# vram_old.net
KiCad netlist of a schematic drawn in Altium Designer
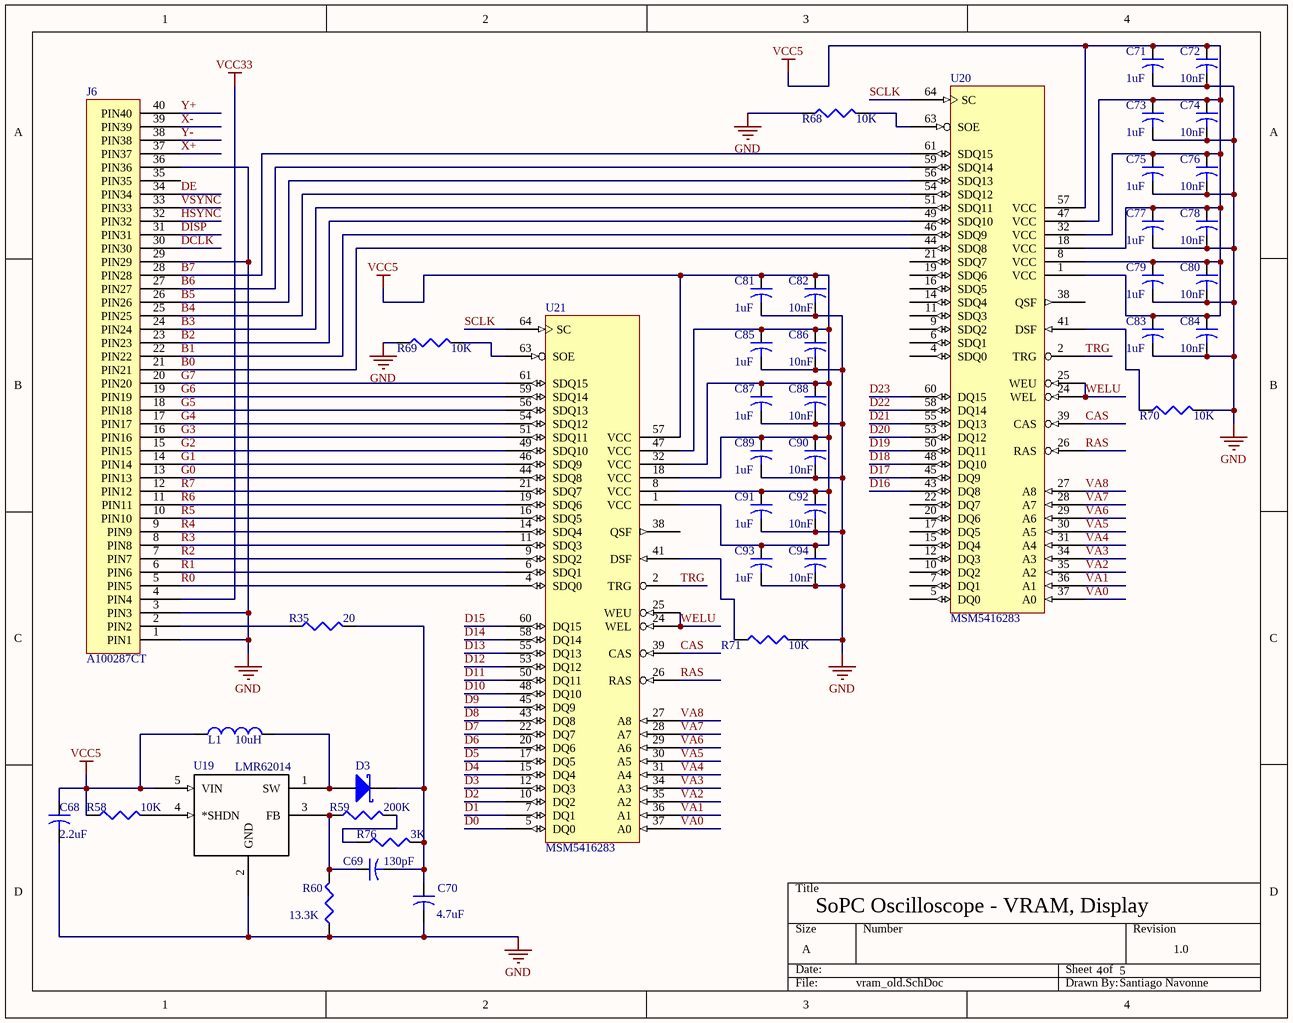
[diagram p0: vram_old.SchDoc]

(export (version "E")
  (design (tool "Eeschema 10.0.6"))
  (components
    (comp (ref "C68")
      (value "2.2uF")
      (footprint "CAPC1608L")
      (description "Capacitor")
      (fields (field (name "Comment") "Cap2") (field (name "PUBLISHER") "Altium Limited"))
      (libsource (lib "Miscellaneous Devices") (part "Cap2"))
    )
    (comp (ref "C69")
      (value "130pF")
      (footprint "CAPC2012N")
      (description "Capacitor")
      (fields (field (name "Comment") "Cap2") (field (name "PUBLISHER") "Altium Limited"))
      (libsource (lib "Miscellaneous Devices") (part "Cap2"))
    )
    (comp (ref "C70")
      (value "4.7uF")
      (footprint "CAPC1608L")
      (description "Capacitor")
      (fields (field (name "Comment") "Cap2") (field (name "PUBLISHER") "Altium Limited"))
      (libsource (lib "Miscellaneous Devices") (part "Cap2"))
    )
    (comp (ref "C71")
      (value "1uF")
      (footprint "CAPC1608L")
      (description "Capacitor")
      (fields (field (name "Comment") "Cap2") (field (name "PUBLISHER") "Altium Limited"))
      (libsource (lib "Miscellaneous Devices") (part "Cap2"))
    )
    (comp (ref "C72")
      (value "10nF")
      (footprint "CAPC1608L")
      (description "Capacitor")
      (fields (field (name "Comment") "Cap2") (field (name "PUBLISHER") "Altium Limited"))
      (libsource (lib "Miscellaneous Devices") (part "Cap2"))
    )
    (comp (ref "C73")
      (value "1uF")
      (footprint "CAPC1608L")
      (description "Capacitor")
      (fields (field (name "Comment") "Cap2") (field (name "PUBLISHER") "Altium Limited"))
      (libsource (lib "Miscellaneous Devices") (part "Cap2"))
    )
    (comp (ref "C74")
      (value "10nF")
      (footprint "CAPC1608L")
      (description "Capacitor")
      (fields (field (name "Comment") "Cap2") (field (name "PUBLISHER") "Altium Limited"))
      (libsource (lib "Miscellaneous Devices") (part "Cap2"))
    )
    (comp (ref "C75")
      (value "1uF")
      (footprint "CAPC1608L")
      (description "Capacitor")
      (fields (field (name "Comment") "Cap2") (field (name "PUBLISHER") "Altium Limited"))
      (libsource (lib "Miscellaneous Devices") (part "Cap2"))
    )
    (comp (ref "C76")
      (value "10nF")
      (footprint "CAPC1608L")
      (description "Capacitor")
      (fields (field (name "Comment") "Cap2") (field (name "PUBLISHER") "Altium Limited"))
      (libsource (lib "Miscellaneous Devices") (part "Cap2"))
    )
    (comp (ref "C77")
      (value "1uF")
      (footprint "CAPC1608L")
      (description "Capacitor")
      (fields (field (name "Comment") "Cap2") (field (name "PUBLISHER") "Altium Limited"))
      (libsource (lib "Miscellaneous Devices") (part "Cap2"))
    )
    (comp (ref "C78")
      (value "10nF")
      (footprint "CAPC1608L")
      (description "Capacitor")
      (fields (field (name "Comment") "Cap2") (field (name "PUBLISHER") "Altium Limited"))
      (libsource (lib "Miscellaneous Devices") (part "Cap2"))
    )
    (comp (ref "C79")
      (value "1uF")
      (footprint "CAPC1608L")
      (description "Capacitor")
      (fields (field (name "Comment") "Cap2") (field (name "PUBLISHER") "Altium Limited"))
      (libsource (lib "Miscellaneous Devices") (part "Cap2"))
    )
    (comp (ref "C80")
      (value "10nF")
      (footprint "CAPC1608L")
      (description "Capacitor")
      (fields (field (name "Comment") "Cap2") (field (name "PUBLISHER") "Altium Limited"))
      (libsource (lib "Miscellaneous Devices") (part "Cap2"))
    )
    (comp (ref "C81")
      (value "1uF")
      (footprint "CAPC1608L")
      (description "Capacitor")
      (fields (field (name "Comment") "Cap2") (field (name "PUBLISHER") "Altium Limited"))
      (libsource (lib "Miscellaneous Devices") (part "Cap2"))
    )
    (comp (ref "C82")
      (value "10nF")
      (footprint "CAPC1608L")
      (description "Capacitor")
      (fields (field (name "Comment") "Cap2") (field (name "PUBLISHER") "Altium Limited"))
      (libsource (lib "Miscellaneous Devices") (part "Cap2"))
    )
    (comp (ref "C83")
      (value "1uF")
      (footprint "CAPC1608L")
      (description "Capacitor")
      (fields (field (name "Comment") "Cap2") (field (name "PUBLISHER") "Altium Limited"))
      (libsource (lib "Miscellaneous Devices") (part "Cap2"))
    )
    (comp (ref "C84")
      (value "10nF")
      (footprint "CAPC1608L")
      (description "Capacitor")
      (fields (field (name "Comment") "Cap2") (field (name "PUBLISHER") "Altium Limited"))
      (libsource (lib "Miscellaneous Devices") (part "Cap2"))
    )
    (comp (ref "C85")
      (value "1uF")
      (footprint "CAPC1608L")
      (description "Capacitor")
      (fields (field (name "Comment") "Cap2") (field (name "PUBLISHER") "Altium Limited"))
      (libsource (lib "Miscellaneous Devices") (part "Cap2"))
    )
    (comp (ref "C86")
      (value "10nF")
      (footprint "CAPC1608L")
      (description "Capacitor")
      (fields (field (name "Comment") "Cap2") (field (name "PUBLISHER") "Altium Limited"))
      (libsource (lib "Miscellaneous Devices") (part "Cap2"))
    )
    (comp (ref "C87")
      (value "1uF")
      (footprint "CAPC1608L")
      (description "Capacitor")
      (fields (field (name "Comment") "Cap2") (field (name "PUBLISHER") "Altium Limited"))
      (libsource (lib "Miscellaneous Devices") (part "Cap2"))
    )
    (comp (ref "C88")
      (value "10nF")
      (footprint "CAPC1608L")
      (description "Capacitor")
      (fields (field (name "Comment") "Cap2") (field (name "PUBLISHER") "Altium Limited"))
      (libsource (lib "Miscellaneous Devices") (part "Cap2"))
    )
    (comp (ref "C89")
      (value "1uF")
      (footprint "CAPC1608L")
      (description "Capacitor")
      (fields (field (name "Comment") "Cap2") (field (name "PUBLISHER") "Altium Limited"))
      (libsource (lib "Miscellaneous Devices") (part "Cap2"))
    )
    (comp (ref "C90")
      (value "10nF")
      (footprint "CAPC1608L")
      (description "Capacitor")
      (fields (field (name "Comment") "Cap2") (field (name "PUBLISHER") "Altium Limited"))
      (libsource (lib "Miscellaneous Devices") (part "Cap2"))
    )
    (comp (ref "C91")
      (value "1uF")
      (footprint "CAPC1608L")
      (description "Capacitor")
      (fields (field (name "Comment") "Cap2") (field (name "PUBLISHER") "Altium Limited"))
      (libsource (lib "Miscellaneous Devices") (part "Cap2"))
    )
    (comp (ref "C92")
      (value "10nF")
      (footprint "CAPC1608L")
      (description "Capacitor")
      (fields (field (name "Comment") "Cap2") (field (name "PUBLISHER") "Altium Limited"))
      (libsource (lib "Miscellaneous Devices") (part "Cap2"))
    )
    (comp (ref "C93")
      (value "1uF")
      (footprint "CAPC1608L")
      (description "Capacitor")
      (fields (field (name "Comment") "Cap2") (field (name "PUBLISHER") "Altium Limited"))
      (libsource (lib "Miscellaneous Devices") (part "Cap2"))
    )
    (comp (ref "C94")
      (value "10nF")
      (footprint "CAPC1608L")
      (description "Capacitor")
      (fields (field (name "Comment") "Cap2") (field (name "PUBLISHER") "Altium Limited"))
      (libsource (lib "Miscellaneous Devices") (part "Cap2"))
    )
    (comp (ref "D3")
      (value "D Schottky")
      (footprint "PowerDI123")
      (description "Schottky Diode")
      (fields (field (name "PUBLISHER") "Altium Limited"))
      (libsource (lib "Miscellaneous Devices") (part "D Schottky"))
    )
    (comp (ref "J6")
      (value "A100287CT")
      (footprint "FPC40")
      (libsource (lib "ee52_tago_sch") (part "A100287CT"))
    )
    (comp (ref "L1")
      (value "10uH")
      (footprint "lsdr0703")
      (description "Inductor")
      (fields (field (name "PUBLISHER") "Altium Limited"))
      (libsource (lib "Miscellaneous Devices") (part "Inductor"))
    )
    (comp (ref "R35")
      (value "20")
      (footprint "RESC1608N")
      (description "Resistor")
      (fields (field (name "Comment") "Res3") (field (name "PUBLISHER") "Altium Limited"))
      (libsource (lib "Miscellaneous Devices") (part "Res3"))
    )
    (comp (ref "R58")
      (value "10K")
      (footprint "RESC1608N")
      (description "Resistor")
      (fields (field (name "Comment") "Res3") (field (name "PUBLISHER") "Altium Limited"))
      (libsource (lib "Miscellaneous Devices") (part "Res3"))
    )
    (comp (ref "R59")
      (value "200K")
      (footprint "RESC1608N")
      (description "Resistor")
      (fields (field (name "Comment") "Res3") (field (name "PUBLISHER") "Altium Limited"))
      (libsource (lib "Miscellaneous Devices") (part "Res3"))
    )
    (comp (ref "R60")
      (value "13.3K")
      (footprint "RESC1608N")
      (description "Resistor")
      (fields (field (name "Comment") "Res3") (field (name "PUBLISHER") "Altium Limited"))
      (libsource (lib "Miscellaneous Devices") (part "Res3"))
    )
    (comp (ref "R68")
      (value "10K")
      (footprint "RESC1608N")
      (description "Resistor")
      (fields (field (name "Comment") "Res3") (field (name "PUBLISHER") "Altium Limited"))
      (libsource (lib "Miscellaneous Devices") (part "Res3"))
    )
    (comp (ref "R69")
      (value "10K")
      (footprint "RESC1608N")
      (description "Resistor")
      (fields (field (name "Comment") "Res3") (field (name "PUBLISHER") "Altium Limited"))
      (libsource (lib "Miscellaneous Devices") (part "Res3"))
    )
    (comp (ref "R70")
      (value "10K")
      (footprint "RESC1608N")
      (description "Resistor")
      (fields (field (name "Comment") "Res3") (field (name "PUBLISHER") "Altium Limited"))
      (libsource (lib "Miscellaneous Devices") (part "Res3"))
    )
    (comp (ref "R71")
      (value "10K")
      (footprint "RESC1608N")
      (description "Resistor")
      (fields (field (name "Comment") "Res3") (field (name "PUBLISHER") "Altium Limited"))
      (libsource (lib "Miscellaneous Devices") (part "Res3"))
    )
    (comp (ref "R76")
      (value "3K")
      (footprint "RESC1608N")
      (description "Resistor")
      (fields (field (name "Comment") "Res3") (field (name "PUBLISHER") "Altium Limited"))
      (libsource (lib "Miscellaneous Devices") (part "Res3"))
    )
    (comp (ref "U19")
      (value "LMR62014")
      (footprint "MF05A")
      (description "Imported")
      (fields
        (field (name "MANUFACTURER") "Texas Instruments")
        (field (name "MANUFACTURER_PART_NUMBER") "lmr62014_dbv_5")
      )
      (libsource (lib "2014-02-09_14-03-09") (part "LMR62014_DBV_5"))
    )
    (comp (ref "U20")
      (value "MSM5416283")
      (footprint "SSOP64")
      (description "262,144-Word x 16-Bit Multiport DRAM")
      (libsource (lib "eecs5x") (part "MSM5416283"))
    )
    (comp (ref "U21")
      (value "MSM5416283")
      (footprint "SSOP64")
      (description "262,144-Word x 16-Bit Multiport DRAM")
      (libsource (lib "eecs5x") (part "MSM5416283"))
    )
  )
  (nets
    (net (code "1") (name "/B0") (class "Default")
      (node (ref "J6") (pin "21") (pinfunction "PIN21_21") (pintype "passive"))
      (node (ref "U20") (pin "44") (pinfunction "SDQ8_44") (pintype "bidirectional"))
    )
    (net (code "2") (name "/B1") (class "Default")
      (node (ref "J6") (pin "22") (pinfunction "PIN22_22") (pintype "passive"))
      (node (ref "U20") (pin "46") (pinfunction "SDQ9_46") (pintype "bidirectional"))
    )
    (net (code "3") (name "/B2") (class "Default")
      (node (ref "J6") (pin "23") (pinfunction "PIN23_23") (pintype "passive"))
      (node (ref "U20") (pin "49") (pinfunction "SDQ10_49") (pintype "bidirectional"))
    )
    (net (code "4") (name "/B3") (class "Default")
      (node (ref "J6") (pin "24") (pinfunction "PIN24_24") (pintype "passive"))
      (node (ref "U20") (pin "51") (pinfunction "SDQ11_51") (pintype "bidirectional"))
    )
    (net (code "5") (name "/B4") (class "Default")
      (node (ref "J6") (pin "25") (pinfunction "PIN25_25") (pintype "passive"))
      (node (ref "U20") (pin "54") (pinfunction "SDQ12_54") (pintype "bidirectional"))
    )
    (net (code "6") (name "/B5") (class "Default")
      (node (ref "J6") (pin "26") (pinfunction "PIN26_26") (pintype "passive"))
      (node (ref "U20") (pin "56") (pinfunction "SDQ13_56") (pintype "bidirectional"))
    )
    (net (code "7") (name "/B6") (class "Default")
      (node (ref "J6") (pin "27") (pinfunction "PIN27_27") (pintype "passive"))
      (node (ref "U20") (pin "59") (pinfunction "SDQ14_59") (pintype "bidirectional"))
    )
    (net (code "8") (name "/B7") (class "Default")
      (node (ref "J6") (pin "28") (pinfunction "PIN28_28") (pintype "passive"))
      (node (ref "U20") (pin "61") (pinfunction "SDQ15_61") (pintype "bidirectional"))
    )
    (net (code "9") (name "/CAS") (class "Default")
      (node (ref "U20") (pin "39") (pinfunction "CAS_39") (pintype "input"))
      (node (ref "U21") (pin "39") (pinfunction "CAS_39") (pintype "input"))
    )
    (net (code "10") (name "/D0") (class "Default")
      (node (ref "U21") (pin "5") (pinfunction "DQ0_5") (pintype "bidirectional"))
    )
    (net (code "11") (name "/D1") (class "Default")
      (node (ref "U21") (pin "7") (pinfunction "DQ1_7") (pintype "bidirectional"))
    )
    (net (code "12") (name "/D2") (class "Default")
      (node (ref "U21") (pin "10") (pinfunction "DQ2_10") (pintype "bidirectional"))
    )
    (net (code "13") (name "/D3") (class "Default")
      (node (ref "U21") (pin "12") (pinfunction "DQ3_12") (pintype "bidirectional"))
    )
    (net (code "14") (name "/D4") (class "Default")
      (node (ref "U21") (pin "15") (pinfunction "DQ4_15") (pintype "bidirectional"))
    )
    (net (code "15") (name "/D5") (class "Default")
      (node (ref "U21") (pin "17") (pinfunction "DQ5_17") (pintype "bidirectional"))
    )
    (net (code "16") (name "/D6") (class "Default")
      (node (ref "U21") (pin "20") (pinfunction "DQ6_20") (pintype "bidirectional"))
    )
    (net (code "17") (name "/D7") (class "Default")
      (node (ref "U21") (pin "22") (pinfunction "DQ7_22") (pintype "bidirectional"))
    )
    (net (code "18") (name "/D8") (class "Default")
      (node (ref "U21") (pin "43") (pinfunction "DQ8_43") (pintype "bidirectional"))
    )
    (net (code "19") (name "/D9") (class "Default")
      (node (ref "U21") (pin "45") (pinfunction "DQ9_45") (pintype "bidirectional"))
    )
    (net (code "20") (name "/D10") (class "Default")
      (node (ref "U21") (pin "48") (pinfunction "DQ10_48") (pintype "bidirectional"))
    )
    (net (code "21") (name "/D11") (class "Default")
      (node (ref "U21") (pin "50") (pinfunction "DQ11_50") (pintype "bidirectional"))
    )
    (net (code "22") (name "/D12") (class "Default")
      (node (ref "U21") (pin "53") (pinfunction "DQ12_53") (pintype "bidirectional"))
    )
    (net (code "23") (name "/D13") (class "Default")
      (node (ref "U21") (pin "55") (pinfunction "DQ13_55") (pintype "bidirectional"))
    )
    (net (code "24") (name "/D14") (class "Default")
      (node (ref "U21") (pin "58") (pinfunction "DQ14_58") (pintype "bidirectional"))
    )
    (net (code "25") (name "/D15") (class "Default")
      (node (ref "U21") (pin "60") (pinfunction "DQ15_60") (pintype "bidirectional"))
    )
    (net (code "26") (name "/D16") (class "Default")
      (node (ref "U20") (pin "43") (pinfunction "DQ8_43") (pintype "bidirectional"))
    )
    (net (code "27") (name "/D17") (class "Default")
      (node (ref "U20") (pin "45") (pinfunction "DQ9_45") (pintype "bidirectional"))
    )
    (net (code "28") (name "/D18") (class "Default")
      (node (ref "U20") (pin "48") (pinfunction "DQ10_48") (pintype "bidirectional"))
    )
    (net (code "29") (name "/D19") (class "Default")
      (node (ref "U20") (pin "50") (pinfunction "DQ11_50") (pintype "bidirectional"))
    )
    (net (code "30") (name "/D20") (class "Default")
      (node (ref "U20") (pin "53") (pinfunction "DQ12_53") (pintype "bidirectional"))
    )
    (net (code "31") (name "/D21") (class "Default")
      (node (ref "U20") (pin "55") (pinfunction "DQ13_55") (pintype "bidirectional"))
    )
    (net (code "32") (name "/D22") (class "Default")
      (node (ref "U20") (pin "58") (pinfunction "DQ14_58") (pintype "bidirectional"))
    )
    (net (code "33") (name "/D23") (class "Default")
      (node (ref "U20") (pin "60") (pinfunction "DQ15_60") (pintype "bidirectional"))
    )
    (net (code "34") (name "/DCLK") (class "Default")
      (node (ref "J6") (pin "30") (pinfunction "PIN30_30") (pintype "passive"))
    )
    (net (code "35") (name "/DE") (class "Default")
      (node (ref "J6") (pin "34") (pinfunction "PIN34_34") (pintype "passive"))
    )
    (net (code "36") (name "/DISP") (class "Default")
      (node (ref "J6") (pin "31") (pinfunction "PIN31_31") (pintype "passive"))
    )
    (net (code "37") (name "/G0") (class "Default")
      (node (ref "J6") (pin "13") (pinfunction "PIN13_13") (pintype "passive"))
      (node (ref "U21") (pin "44") (pinfunction "SDQ8_44") (pintype "bidirectional"))
    )
    (net (code "38") (name "/G1") (class "Default")
      (node (ref "J6") (pin "14") (pinfunction "PIN14_14") (pintype "passive"))
      (node (ref "U21") (pin "46") (pinfunction "SDQ9_46") (pintype "bidirectional"))
    )
    (net (code "39") (name "/G2") (class "Default")
      (node (ref "J6") (pin "15") (pinfunction "PIN15_15") (pintype "passive"))
      (node (ref "U21") (pin "49") (pinfunction "SDQ10_49") (pintype "bidirectional"))
    )
    (net (code "40") (name "/G3") (class "Default")
      (node (ref "J6") (pin "16") (pinfunction "PIN16_16") (pintype "passive"))
      (node (ref "U21") (pin "51") (pinfunction "SDQ11_51") (pintype "bidirectional"))
    )
    (net (code "41") (name "/G4") (class "Default")
      (node (ref "J6") (pin "17") (pinfunction "PIN17_17") (pintype "passive"))
      (node (ref "U21") (pin "54") (pinfunction "SDQ12_54") (pintype "bidirectional"))
    )
    (net (code "42") (name "/G5") (class "Default")
      (node (ref "J6") (pin "18") (pinfunction "PIN18_18") (pintype "passive"))
      (node (ref "U21") (pin "56") (pinfunction "SDQ13_56") (pintype "bidirectional"))
    )
    (net (code "43") (name "/G6") (class "Default")
      (node (ref "J6") (pin "19") (pinfunction "PIN19_19") (pintype "passive"))
      (node (ref "U21") (pin "59") (pinfunction "SDQ14_59") (pintype "bidirectional"))
    )
    (net (code "44") (name "/G7") (class "Default")
      (node (ref "J6") (pin "20") (pinfunction "PIN20_20") (pintype "passive"))
      (node (ref "U21") (pin "61") (pinfunction "SDQ15_61") (pintype "bidirectional"))
    )
    (net (code "45") (name "/HSYNC") (class "Default")
      (node (ref "J6") (pin "32") (pinfunction "PIN32_32") (pintype "passive"))
    )
    (net (code "46") (name "/R0") (class "Default")
      (node (ref "J6") (pin "5") (pinfunction "PIN5_5") (pintype "passive"))
      (node (ref "U21") (pin "4") (pinfunction "SDQ0_4") (pintype "bidirectional"))
    )
    (net (code "47") (name "/R1") (class "Default")
      (node (ref "J6") (pin "6") (pinfunction "PIN6_6") (pintype "passive"))
      (node (ref "U21") (pin "6") (pinfunction "SDQ1_6") (pintype "bidirectional"))
    )
    (net (code "48") (name "/R2") (class "Default")
      (node (ref "J6") (pin "7") (pinfunction "PIN7_7") (pintype "passive"))
      (node (ref "U21") (pin "9") (pinfunction "SDQ2_9") (pintype "bidirectional"))
    )
    (net (code "49") (name "/R3") (class "Default")
      (node (ref "J6") (pin "8") (pinfunction "PIN8_8") (pintype "passive"))
      (node (ref "U21") (pin "11") (pinfunction "SDQ3_11") (pintype "bidirectional"))
    )
    (net (code "50") (name "/R4") (class "Default")
      (node (ref "J6") (pin "9") (pinfunction "PIN9_9") (pintype "passive"))
      (node (ref "U21") (pin "14") (pinfunction "SDQ4_14") (pintype "bidirectional"))
    )
    (net (code "51") (name "/R5") (class "Default")
      (node (ref "J6") (pin "10") (pinfunction "PIN10_10") (pintype "passive"))
      (node (ref "U21") (pin "16") (pinfunction "SDQ5_16") (pintype "bidirectional"))
    )
    (net (code "52") (name "/R6") (class "Default")
      (node (ref "J6") (pin "11") (pinfunction "PIN11_11") (pintype "passive"))
      (node (ref "U21") (pin "19") (pinfunction "SDQ6_19") (pintype "bidirectional"))
    )
    (net (code "53") (name "/R7") (class "Default")
      (node (ref "J6") (pin "12") (pinfunction "PIN12_12") (pintype "passive"))
      (node (ref "U21") (pin "21") (pinfunction "SDQ7_21") (pintype "bidirectional"))
    )
    (net (code "54") (name "/RAS") (class "Default")
      (node (ref "U20") (pin "26") (pinfunction "RAS_26") (pintype "input"))
      (node (ref "U21") (pin "26") (pinfunction "RAS_26") (pintype "input"))
    )
    (net (code "55") (name "/SCLK") (class "Default")
      (node (ref "U20") (pin "64") (pinfunction "SC_64") (pintype "input"))
      (node (ref "U21") (pin "64") (pinfunction "SC_64") (pintype "input"))
    )
    (net (code "56") (name "/TRG") (class "Default")
      (node (ref "U20") (pin "2") (pinfunction "TRG_2") (pintype "passive"))
      (node (ref "U21") (pin "2") (pinfunction "TRG_2") (pintype "passive"))
    )
    (net (code "57") (name "/VA0") (class "Default")
      (node (ref "U20") (pin "37") (pinfunction "A0_37") (pintype "input"))
      (node (ref "U21") (pin "37") (pinfunction "A0_37") (pintype "input"))
    )
    (net (code "58") (name "/VA1") (class "Default")
      (node (ref "U20") (pin "36") (pinfunction "A1_36") (pintype "input"))
      (node (ref "U21") (pin "36") (pinfunction "A1_36") (pintype "input"))
    )
    (net (code "59") (name "/VA2") (class "Default")
      (node (ref "U20") (pin "35") (pinfunction "A2_35") (pintype "input"))
      (node (ref "U21") (pin "35") (pinfunction "A2_35") (pintype "input"))
    )
    (net (code "60") (name "/VA3") (class "Default")
      (node (ref "U20") (pin "34") (pinfunction "A3_34") (pintype "input"))
      (node (ref "U21") (pin "34") (pinfunction "A3_34") (pintype "input"))
    )
    (net (code "61") (name "/VA4") (class "Default")
      (node (ref "U20") (pin "31") (pinfunction "A4_31") (pintype "input"))
      (node (ref "U21") (pin "31") (pinfunction "A4_31") (pintype "input"))
    )
    (net (code "62") (name "/VA5") (class "Default")
      (node (ref "U20") (pin "30") (pinfunction "A5_30") (pintype "input"))
      (node (ref "U21") (pin "30") (pinfunction "A5_30") (pintype "input"))
    )
    (net (code "63") (name "/VA6") (class "Default")
      (node (ref "U20") (pin "29") (pinfunction "A6_29") (pintype "input"))
      (node (ref "U21") (pin "29") (pinfunction "A6_29") (pintype "input"))
    )
    (net (code "64") (name "/VA7") (class "Default")
      (node (ref "U20") (pin "28") (pinfunction "A7_28") (pintype "input"))
      (node (ref "U21") (pin "28") (pinfunction "A7_28") (pintype "input"))
    )
    (net (code "65") (name "/VA8") (class "Default")
      (node (ref "U20") (pin "27") (pinfunction "A8_27") (pintype "input"))
      (node (ref "U21") (pin "27") (pinfunction "A8_27") (pintype "input"))
    )
    (net (code "66") (name "/VSYNC") (class "Default")
      (node (ref "J6") (pin "33") (pinfunction "PIN33_33") (pintype "passive"))
    )
    (net (code "67") (name "/WELU") (class "Default")
      (node (ref "U20") (pin "24") (pinfunction "WEL_24") (pintype "input"))
      (node (ref "U20") (pin "25") (pinfunction "WEU_25") (pintype "input"))
      (node (ref "U21") (pin "24") (pinfunction "WEL_24") (pintype "input"))
      (node (ref "U21") (pin "25") (pinfunction "WEU_25") (pintype "input"))
    )
    (net (code "68") (name "/X+") (class "Default")
      (node (ref "J6") (pin "37") (pinfunction "PIN37_37") (pintype "passive"))
    )
    (net (code "69") (name "/X-") (class "Default")
      (node (ref "J6") (pin "39") (pinfunction "PIN39_39") (pintype "passive"))
    )
    (net (code "70") (name "/Y+") (class "Default")
      (node (ref "J6") (pin "40") (pinfunction "PIN40_40") (pintype "passive"))
    )
    (net (code "71") (name "/Y-") (class "Default")
      (node (ref "J6") (pin "38") (pinfunction "PIN38_38") (pintype "passive"))
    )
    (net (code "72") (name "GND") (class "Default")
      (node (ref "C68") (pin "2") (pinfunction "2_2") (pintype "passive"))
      (node (ref "C70") (pin "2") (pinfunction "2_2") (pintype "passive"))
      (node (ref "C71") (pin "2") (pinfunction "2_2") (pintype "passive"))
      (node (ref "C72") (pin "2") (pinfunction "2_2") (pintype "passive"))
      (node (ref "C73") (pin "2") (pinfunction "2_2") (pintype "passive"))
      (node (ref "C74") (pin "2") (pinfunction "2_2") (pintype "passive"))
      (node (ref "C75") (pin "2") (pinfunction "2_2") (pintype "passive"))
      (node (ref "C76") (pin "2") (pinfunction "2_2") (pintype "passive"))
      (node (ref "C77") (pin "2") (pinfunction "2_2") (pintype "passive"))
      (node (ref "C78") (pin "2") (pinfunction "2_2") (pintype "passive"))
      (node (ref "C79") (pin "2") (pinfunction "2_2") (pintype "passive"))
      (node (ref "C80") (pin "2") (pinfunction "2_2") (pintype "passive"))
      (node (ref "C81") (pin "2") (pinfunction "2_2") (pintype "passive"))
      (node (ref "C82") (pin "2") (pinfunction "2_2") (pintype "passive"))
      (node (ref "C83") (pin "2") (pinfunction "2_2") (pintype "passive"))
      (node (ref "C84") (pin "2") (pinfunction "2_2") (pintype "passive"))
      (node (ref "C85") (pin "2") (pinfunction "2_2") (pintype "passive"))
      (node (ref "C86") (pin "2") (pinfunction "2_2") (pintype "passive"))
      (node (ref "C87") (pin "2") (pinfunction "2_2") (pintype "passive"))
      (node (ref "C88") (pin "2") (pinfunction "2_2") (pintype "passive"))
      (node (ref "C89") (pin "2") (pinfunction "2_2") (pintype "passive"))
      (node (ref "C90") (pin "2") (pinfunction "2_2") (pintype "passive"))
      (node (ref "C91") (pin "2") (pinfunction "2_2") (pintype "passive"))
      (node (ref "C92") (pin "2") (pinfunction "2_2") (pintype "passive"))
      (node (ref "C93") (pin "2") (pinfunction "2_2") (pintype "passive"))
      (node (ref "C94") (pin "2") (pinfunction "2_2") (pintype "passive"))
      (node (ref "J6") (pin "1") (pinfunction "PIN1_1") (pintype "passive"))
      (node (ref "J6") (pin "29") (pinfunction "PIN29_29") (pintype "passive"))
      (node (ref "J6") (pin "3") (pinfunction "PIN3_3") (pintype "passive"))
      (node (ref "J6") (pin "36") (pinfunction "PIN36_36") (pintype "passive"))
      (node (ref "R60") (pin "1") (pinfunction "1_1") (pintype "passive"))
      (node (ref "R68") (pin "1") (pinfunction "1_1") (pintype "passive"))
      (node (ref "R69") (pin "1") (pinfunction "1_1") (pintype "passive"))
      (node (ref "R70") (pin "2") (pinfunction "2_2") (pintype "passive"))
      (node (ref "R71") (pin "2") (pinfunction "2_2") (pintype "passive"))
      (node (ref "U19") (pin "2") (pinfunction "GND_2") (pintype "power_in"))
      (node (ref "U20") (pin "13") (pinfunction "GND_13") (pintype "power_in"))
      (node (ref "U20") (pin "23") (pinfunction "GND_23") (pintype "power_in"))
      (node (ref "U20") (pin "3") (pinfunction "GND_3") (pintype "power_in"))
      (node (ref "U20") (pin "33") (pinfunction "GND_33") (pintype "power_in"))
      (node (ref "U20") (pin "42") (pinfunction "GND_42") (pintype "power_in"))
      (node (ref "U20") (pin "52") (pinfunction "GND_52") (pintype "power_in"))
      (node (ref "U20") (pin "62") (pinfunction "GND_62") (pintype "power_in"))
      (node (ref "U21") (pin "13") (pinfunction "GND_13") (pintype "power_in"))
      (node (ref "U21") (pin "23") (pinfunction "GND_23") (pintype "power_in"))
      (node (ref "U21") (pin "3") (pinfunction "GND_3") (pintype "power_in"))
      (node (ref "U21") (pin "33") (pinfunction "GND_33") (pintype "power_in"))
      (node (ref "U21") (pin "42") (pinfunction "GND_42") (pintype "power_in"))
      (node (ref "U21") (pin "52") (pinfunction "GND_52") (pintype "power_in"))
      (node (ref "U21") (pin "62") (pinfunction "GND_62") (pintype "power_in"))
    )
    (net (code "73") (name "Net-(C69-Pad2)") (class "Default")
      (node (ref "C69") (pin "2") (pinfunction "2_2") (pintype "passive"))
      (node (ref "C70") (pin "1") (pinfunction "1_1") (pintype "passive"))
      (node (ref "D3") (pin "K") (pinfunction "K_K") (pintype "passive"))
      (node (ref "R35") (pin "2") (pinfunction "2_2") (pintype "passive"))
      (node (ref "R76") (pin "2") (pinfunction "2_2") (pintype "passive"))
    )
    (net (code "74") (name "Net-(J6-PIN2)") (class "Default")
      (node (ref "J6") (pin "2") (pinfunction "PIN2_2") (pintype "passive"))
      (node (ref "R35") (pin "1") (pinfunction "1_1") (pintype "passive"))
    )
    (net (code "75") (name "Net-(R59-Pad2)") (class "Default")
      (node (ref "R59") (pin "2") (pinfunction "2_2") (pintype "passive"))
      (node (ref "R76") (pin "1") (pinfunction "1_1") (pintype "passive"))
    )
    (net (code "76") (name "Net-(U19-*SHDN)") (class "Default")
      (node (ref "R58") (pin "2") (pinfunction "2_2") (pintype "passive"))
      (node (ref "U19") (pin "4") (pinfunction "*SHDN_4") (pintype "input"))
    )
    (net (code "77") (name "Net-(U19-FB)") (class "Default")
      (node (ref "C69") (pin "1") (pinfunction "1_1") (pintype "passive"))
      (node (ref "R59") (pin "1") (pinfunction "1_1") (pintype "passive"))
      (node (ref "R60") (pin "2") (pinfunction "2_2") (pintype "passive"))
      (node (ref "U19") (pin "3") (pinfunction "FB_3") (pintype "passive"))
    )
    (net (code "78") (name "Net-(U19-SW)") (class "Default")
      (node (ref "D3") (pin "A") (pinfunction "A_A") (pintype "passive"))
      (node (ref "L1") (pin "2") (pinfunction "2_2") (pintype "passive"))
      (node (ref "U19") (pin "1") (pinfunction "SW_1") (pintype "passive"))
    )
    (net (code "79") (name "Net-(U20-DSF)") (class "Default")
      (node (ref "R70") (pin "1") (pinfunction "1_1") (pintype "passive"))
      (node (ref "U20") (pin "41") (pinfunction "DSF_41") (pintype "input"))
    )
    (net (code "80") (name "Net-(U20-SOE)") (class "Default")
      (node (ref "R68") (pin "2") (pinfunction "2_2") (pintype "passive"))
      (node (ref "U20") (pin "63") (pinfunction "SOE_63") (pintype "input"))
    )
    (net (code "81") (name "Net-(U21-DSF)") (class "Default")
      (node (ref "R71") (pin "1") (pinfunction "1_1") (pintype "passive"))
      (node (ref "U21") (pin "41") (pinfunction "DSF_41") (pintype "input"))
    )
    (net (code "82") (name "Net-(U21-SOE)") (class "Default")
      (node (ref "R69") (pin "2") (pinfunction "2_2") (pintype "passive"))
      (node (ref "U21") (pin "63") (pinfunction "SOE_63") (pintype "input"))
    )
    (net (code "83") (name "VCC5") (class "Default")
      (node (ref "C68") (pin "1") (pinfunction "1_1") (pintype "passive"))
      (node (ref "C71") (pin "1") (pinfunction "1_1") (pintype "passive"))
      (node (ref "C72") (pin "1") (pinfunction "1_1") (pintype "passive"))
      (node (ref "C73") (pin "1") (pinfunction "1_1") (pintype "passive"))
      (node (ref "C74") (pin "1") (pinfunction "1_1") (pintype "passive"))
      (node (ref "C75") (pin "1") (pinfunction "1_1") (pintype "passive"))
      (node (ref "C76") (pin "1") (pinfunction "1_1") (pintype "passive"))
      (node (ref "C77") (pin "1") (pinfunction "1_1") (pintype "passive"))
      (node (ref "C78") (pin "1") (pinfunction "1_1") (pintype "passive"))
      (node (ref "C79") (pin "1") (pinfunction "1_1") (pintype "passive"))
      (node (ref "C80") (pin "1") (pinfunction "1_1") (pintype "passive"))
      (node (ref "C81") (pin "1") (pinfunction "1_1") (pintype "passive"))
      (node (ref "C82") (pin "1") (pinfunction "1_1") (pintype "passive"))
      (node (ref "C83") (pin "1") (pinfunction "1_1") (pintype "passive"))
      (node (ref "C84") (pin "1") (pinfunction "1_1") (pintype "passive"))
      (node (ref "C85") (pin "1") (pinfunction "1_1") (pintype "passive"))
      (node (ref "C86") (pin "1") (pinfunction "1_1") (pintype "passive"))
      (node (ref "C87") (pin "1") (pinfunction "1_1") (pintype "passive"))
      (node (ref "C88") (pin "1") (pinfunction "1_1") (pintype "passive"))
      (node (ref "C89") (pin "1") (pinfunction "1_1") (pintype "passive"))
      (node (ref "C90") (pin "1") (pinfunction "1_1") (pintype "passive"))
      (node (ref "C91") (pin "1") (pinfunction "1_1") (pintype "passive"))
      (node (ref "C92") (pin "1") (pinfunction "1_1") (pintype "passive"))
      (node (ref "C93") (pin "1") (pinfunction "1_1") (pintype "passive"))
      (node (ref "C94") (pin "1") (pinfunction "1_1") (pintype "passive"))
      (node (ref "L1") (pin "1") (pinfunction "1_1") (pintype "passive"))
      (node (ref "R58") (pin "1") (pinfunction "1_1") (pintype "passive"))
      (node (ref "U19") (pin "5") (pinfunction "VIN_5") (pintype "input"))
      (node (ref "U20") (pin "1") (pinfunction "VCC_1") (pintype "power_in"))
      (node (ref "U20") (pin "18") (pinfunction "VCC_18") (pintype "power_in"))
      (node (ref "U20") (pin "32") (pinfunction "VCC_32") (pintype "power_in"))
      (node (ref "U20") (pin "47") (pinfunction "VCC_47") (pintype "power_in"))
      (node (ref "U20") (pin "57") (pinfunction "VCC_57") (pintype "power_in"))
      (node (ref "U20") (pin "8") (pinfunction "VCC_8") (pintype "power_in"))
      (node (ref "U21") (pin "1") (pinfunction "VCC_1") (pintype "power_in"))
      (node (ref "U21") (pin "18") (pinfunction "VCC_18") (pintype "power_in"))
      (node (ref "U21") (pin "32") (pinfunction "VCC_32") (pintype "power_in"))
      (node (ref "U21") (pin "47") (pinfunction "VCC_47") (pintype "power_in"))
      (node (ref "U21") (pin "57") (pinfunction "VCC_57") (pintype "power_in"))
      (node (ref "U21") (pin "8") (pinfunction "VCC_8") (pintype "power_in"))
    )
    (net (code "84") (name "VCC33") (class "Default")
      (node (ref "J6") (pin "4") (pinfunction "PIN4_4") (pintype "passive"))
    )
    (net (code "85") (name "unconnected-(J6-PIN35-Pad35)") (class "Default")
      (node (ref "J6") (pin "35") (pinfunction "PIN35_35") (pintype "passive"))
    )
    (net (code "86") (name "unconnected-(U20-DQ0-Pad5)") (class "Default")
      (node (ref "U20") (pin "5") (pinfunction "DQ0_5") (pintype "bidirectional"))
    )
    (net (code "87") (name "unconnected-(U20-DQ1-Pad7)") (class "Default")
      (node (ref "U20") (pin "7") (pinfunction "DQ1_7") (pintype "bidirectional"))
    )
    (net (code "88") (name "unconnected-(U20-DQ2-Pad10)") (class "Default")
      (node (ref "U20") (pin "10") (pinfunction "DQ2_10") (pintype "bidirectional"))
    )
    (net (code "89") (name "unconnected-(U20-DQ3-Pad12)") (class "Default")
      (node (ref "U20") (pin "12") (pinfunction "DQ3_12") (pintype "bidirectional"))
    )
    (net (code "90") (name "unconnected-(U20-DQ4-Pad15)") (class "Default")
      (node (ref "U20") (pin "15") (pinfunction "DQ4_15") (pintype "bidirectional"))
    )
    (net (code "91") (name "unconnected-(U20-DQ5-Pad17)") (class "Default")
      (node (ref "U20") (pin "17") (pinfunction "DQ5_17") (pintype "bidirectional"))
    )
    (net (code "92") (name "unconnected-(U20-DQ6-Pad20)") (class "Default")
      (node (ref "U20") (pin "20") (pinfunction "DQ6_20") (pintype "bidirectional"))
    )
    (net (code "93") (name "unconnected-(U20-DQ7-Pad22)") (class "Default")
      (node (ref "U20") (pin "22") (pinfunction "DQ7_22") (pintype "bidirectional"))
    )
    (net (code "94") (name "unconnected-(U20-QSF-Pad38)") (class "Default")
      (node (ref "U20") (pin "38") (pinfunction "QSF_38") (pintype "output"))
    )
    (net (code "95") (name "unconnected-(U20-SDQ0-Pad4)") (class "Default")
      (node (ref "U20") (pin "4") (pinfunction "SDQ0_4") (pintype "bidirectional"))
    )
    (net (code "96") (name "unconnected-(U20-SDQ1-Pad6)") (class "Default")
      (node (ref "U20") (pin "6") (pinfunction "SDQ1_6") (pintype "bidirectional"))
    )
    (net (code "97") (name "unconnected-(U20-SDQ2-Pad9)") (class "Default")
      (node (ref "U20") (pin "9") (pinfunction "SDQ2_9") (pintype "bidirectional"))
    )
    (net (code "98") (name "unconnected-(U20-SDQ3-Pad11)") (class "Default")
      (node (ref "U20") (pin "11") (pinfunction "SDQ3_11") (pintype "bidirectional"))
    )
    (net (code "99") (name "unconnected-(U20-SDQ4-Pad14)") (class "Default")
      (node (ref "U20") (pin "14") (pinfunction "SDQ4_14") (pintype "bidirectional"))
    )
    (net (code "100") (name "unconnected-(U20-SDQ5-Pad16)") (class "Default")
      (node (ref "U20") (pin "16") (pinfunction "SDQ5_16") (pintype "bidirectional"))
    )
    (net (code "101") (name "unconnected-(U20-SDQ6-Pad19)") (class "Default")
      (node (ref "U20") (pin "19") (pinfunction "SDQ6_19") (pintype "bidirectional"))
    )
    (net (code "102") (name "unconnected-(U20-SDQ7-Pad21)") (class "Default")
      (node (ref "U20") (pin "21") (pinfunction "SDQ7_21") (pintype "bidirectional"))
    )
    (net (code "103") (name "unconnected-(U21-QSF-Pad38)") (class "Default")
      (node (ref "U21") (pin "38") (pinfunction "QSF_38") (pintype "output"))
    )
  )
)
